# schematic_v2.net
KiCad netlist of a schematic drawn in EAGLE
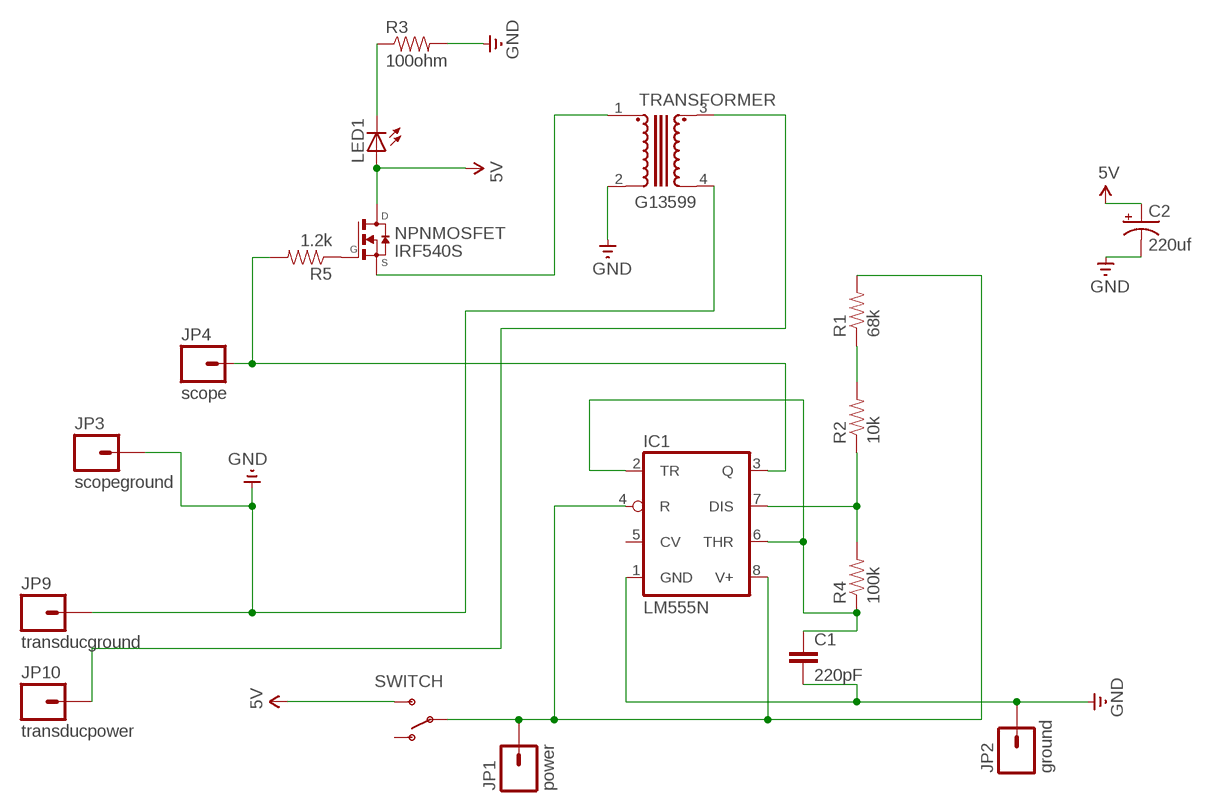
[diagram p0: schematic, sheet 1]

(export (version "E")
  (design (tool "Eeschema 10.0.6"))
  (components
    (comp (ref "C1")
      (value "220pF")
      (footprint "eagle-import:CAP-PTH-SMALL-KIT")
      (libsource (lib "eagle-import") (part "CAPKIT"))
    )
    (comp (ref "C2")
      (value "220uf")
      (footprint "eagle-import:PANASONIC_D")
      (libsource (lib "eagle-import") (part "CAP_POLD"))
    )
    (comp (ref "IC1")
      (value "LM555N")
      (footprint "eagle-import:DIL08")
      (libsource (lib "eagle-import") (part "555NLM"))
    )
    (comp (ref "JP1")
      (value "power")
      (footprint "eagle-import:1X01_OFFSET")
      (libsource (lib "eagle-import") (part "M01OFFSET"))
    )
    (comp (ref "JP2")
      (value "ground")
      (footprint "eagle-import:1X01_OFFSET")
      (libsource (lib "eagle-import") (part "M01OFFSET"))
    )
    (comp (ref "JP3")
      (value "scopeground")
      (footprint "eagle-import:1X01_OFFSET")
      (libsource (lib "eagle-import") (part "M01OFFSET"))
    )
    (comp (ref "JP4")
      (value "scope")
      (footprint "eagle-import:1X01_OFFSET")
      (libsource (lib "eagle-import") (part "M01OFFSET"))
    )
    (comp (ref "JP9")
      (value "transducground")
      (footprint "eagle-import:1X01_OFFSET")
      (libsource (lib "eagle-import") (part "M01OFFSET"))
    )
    (comp (ref "JP10")
      (value "transducpower")
      (footprint "eagle-import:1X01_OFFSET")
      (libsource (lib "eagle-import") (part "M01OFFSET"))
    )
    (comp (ref "LED1")
      (value "LED3MM")
      (footprint "eagle-import:LED3MM")
      (libsource (lib "eagle-import") (part "LED3MM"))
    )
    (comp (ref "NPNMOSFET")
      (value "IRF540S")
      (footprint "eagle-import:DPAK")
      (libsource (lib "eagle-import") (part "VND7NV04"))
    )
    (comp (ref "R1")
      (value "68k")
      (footprint "eagle-import:AXIAL-0.3EZ")
      (libsource (lib "eagle-import") (part "RESISTOREZ"))
    )
    (comp (ref "R2")
      (value "10k")
      (footprint "eagle-import:AXIAL-0.3EZ")
      (libsource (lib "eagle-import") (part "RESISTOREZ"))
    )
    (comp (ref "R3")
      (value "100ohm")
      (footprint "eagle-import:AXIAL-0.3EZ")
      (libsource (lib "eagle-import") (part "RESISTOREZ"))
    )
    (comp (ref "R4")
      (value "100k")
      (footprint "eagle-import:AXIAL-0.3EZ")
      (libsource (lib "eagle-import") (part "RESISTOREZ"))
    )
    (comp (ref "R5")
      (value "1.2k")
      (footprint "eagle-import:AXIAL-0.3EZ")
      (libsource (lib "eagle-import") (part "RESISTOREZ"))
    )
    (comp (ref "SWITCH")
      (value "SWITCH-SPDTPTH")
      (footprint "eagle-import:SWITCH-SPDT")
      (libsource (lib "eagle-import") (part "SWITCH-SPDTPTH"))
    )
    (comp (ref "TRANSFORMER")
      (value "G13599")
      (footprint "eagle-import:REDSPEC-1")
      (libsource (lib "eagle-import") (part "SP-33"))
    )
  )
  (nets
    (net (code "1") (name "5V") (class "Default")
      (node (ref "C2") (pin "+") (pinfunction "+_+") (pintype "passive"))
      (node (ref "LED1") (pin "A") (pinfunction "A_A") (pintype "passive"))
      (node (ref "NPNMOSFET") (pin "4") (pinfunction "D_4") (pintype "passive"))
      (node (ref "SWITCH") (pin "3") (pinfunction "S_3") (pintype "passive"))
    )
    (net (code "2") (name "GND") (class "Default")
      (node (ref "C1") (pin "2") (pinfunction "2_2") (pintype "passive"))
      (node (ref "C2") (pin "-") (pinfunction "-_-") (pintype "passive"))
      (node (ref "IC1") (pin "1") (pinfunction "GND_1") (pintype "power_in"))
      (node (ref "JP2") (pin "1") (pinfunction "1_1") (pintype "passive"))
      (node (ref "JP3") (pin "1") (pinfunction "1_1") (pintype "passive"))
      (node (ref "JP9") (pin "1") (pinfunction "1_1") (pintype "passive"))
      (node (ref "R3") (pin "P$2") (pinfunction "2_P$2") (pintype "passive"))
      (node (ref "TRANSFORMER") (pin "2") (pinfunction "2_2") (pintype "passive"))
      (node (ref "TRANSFORMER") (pin "4") (pinfunction "4_4") (pintype "passive"))
    )
    (net (code "3") (name "Net-(IC1-DIS)") (class "Default")
      (node (ref "IC1") (pin "7") (pinfunction "DIS_7") (pintype "input"))
      (node (ref "R2") (pin "P$1") (pinfunction "1_P$1") (pintype "passive"))
      (node (ref "R4") (pin "P$2") (pinfunction "2_P$2") (pintype "passive"))
    )
    (net (code "4") (name "Net-(IC1-Q)") (class "Default")
      (node (ref "IC1") (pin "3") (pinfunction "Q_3") (pintype "output"))
      (node (ref "JP4") (pin "1") (pinfunction "1_1") (pintype "passive"))
      (node (ref "R5") (pin "P$2") (pinfunction "2_P$2") (pintype "passive"))
    )
    (net (code "5") (name "Net-(IC1-R)") (class "Default")
      (node (ref "IC1") (pin "4") (pinfunction "R_4") (pintype "input"))
      (node (ref "IC1") (pin "8") (pinfunction "V+_8") (pintype "power_in"))
      (node (ref "JP1") (pin "1") (pinfunction "1_1") (pintype "passive"))
      (node (ref "R1") (pin "P$2") (pinfunction "2_P$2") (pintype "passive"))
      (node (ref "SWITCH") (pin "2") (pinfunction "P_2") (pintype "passive"))
    )
    (net (code "6") (name "Net-(IC1-THR)") (class "Default")
      (node (ref "C1") (pin "1") (pinfunction "1_1") (pintype "passive"))
      (node (ref "IC1") (pin "2") (pinfunction "TR_2") (pintype "input"))
      (node (ref "IC1") (pin "6") (pinfunction "THR_6") (pintype "input"))
      (node (ref "R4") (pin "P$1") (pinfunction "1_P$1") (pintype "passive"))
    )
    (net (code "7") (name "Net-(JP10-Pad1)") (class "Default")
      (node (ref "JP10") (pin "1") (pinfunction "1_1") (pintype "passive"))
      (node (ref "TRANSFORMER") (pin "3") (pinfunction "3_3") (pintype "passive"))
    )
    (net (code "8") (name "Net-(LED1-C)") (class "Default")
      (node (ref "LED1") (pin "K") (pinfunction "C_K") (pintype "passive"))
      (node (ref "R3") (pin "P$1") (pinfunction "1_P$1") (pintype "passive"))
    )
    (net (code "9") (name "Net-(NPNMOSFET-G)") (class "Default")
      (node (ref "NPNMOSFET") (pin "1") (pinfunction "G_1") (pintype "passive"))
      (node (ref "R5") (pin "P$1") (pinfunction "1_P$1") (pintype "passive"))
    )
    (net (code "10") (name "Net-(NPNMOSFET-S)") (class "Default")
      (node (ref "NPNMOSFET") (pin "3") (pinfunction "S_3") (pintype "passive"))
      (node (ref "TRANSFORMER") (pin "1") (pinfunction "1_1") (pintype "passive"))
    )
    (net (code "11") (name "Net-(R1-1)") (class "Default")
      (node (ref "R1") (pin "P$1") (pinfunction "1_P$1") (pintype "passive"))
      (node (ref "R2") (pin "P$2") (pinfunction "2_P$2") (pintype "passive"))
    )
    (net (code "12") (name "unconnected-(IC1-CV-Pad5)") (class "Default")
      (node (ref "IC1") (pin "5") (pinfunction "CV_5") (pintype "input"))
    )
    (net (code "13") (name "unconnected-(SWITCH-O-Pad1)") (class "Default")
      (node (ref "SWITCH") (pin "1") (pinfunction "O_1") (pintype "passive"))
    )
  )
)
